# AMS_MCU.net
KiCad netlist of a schematic drawn in Altium Designer
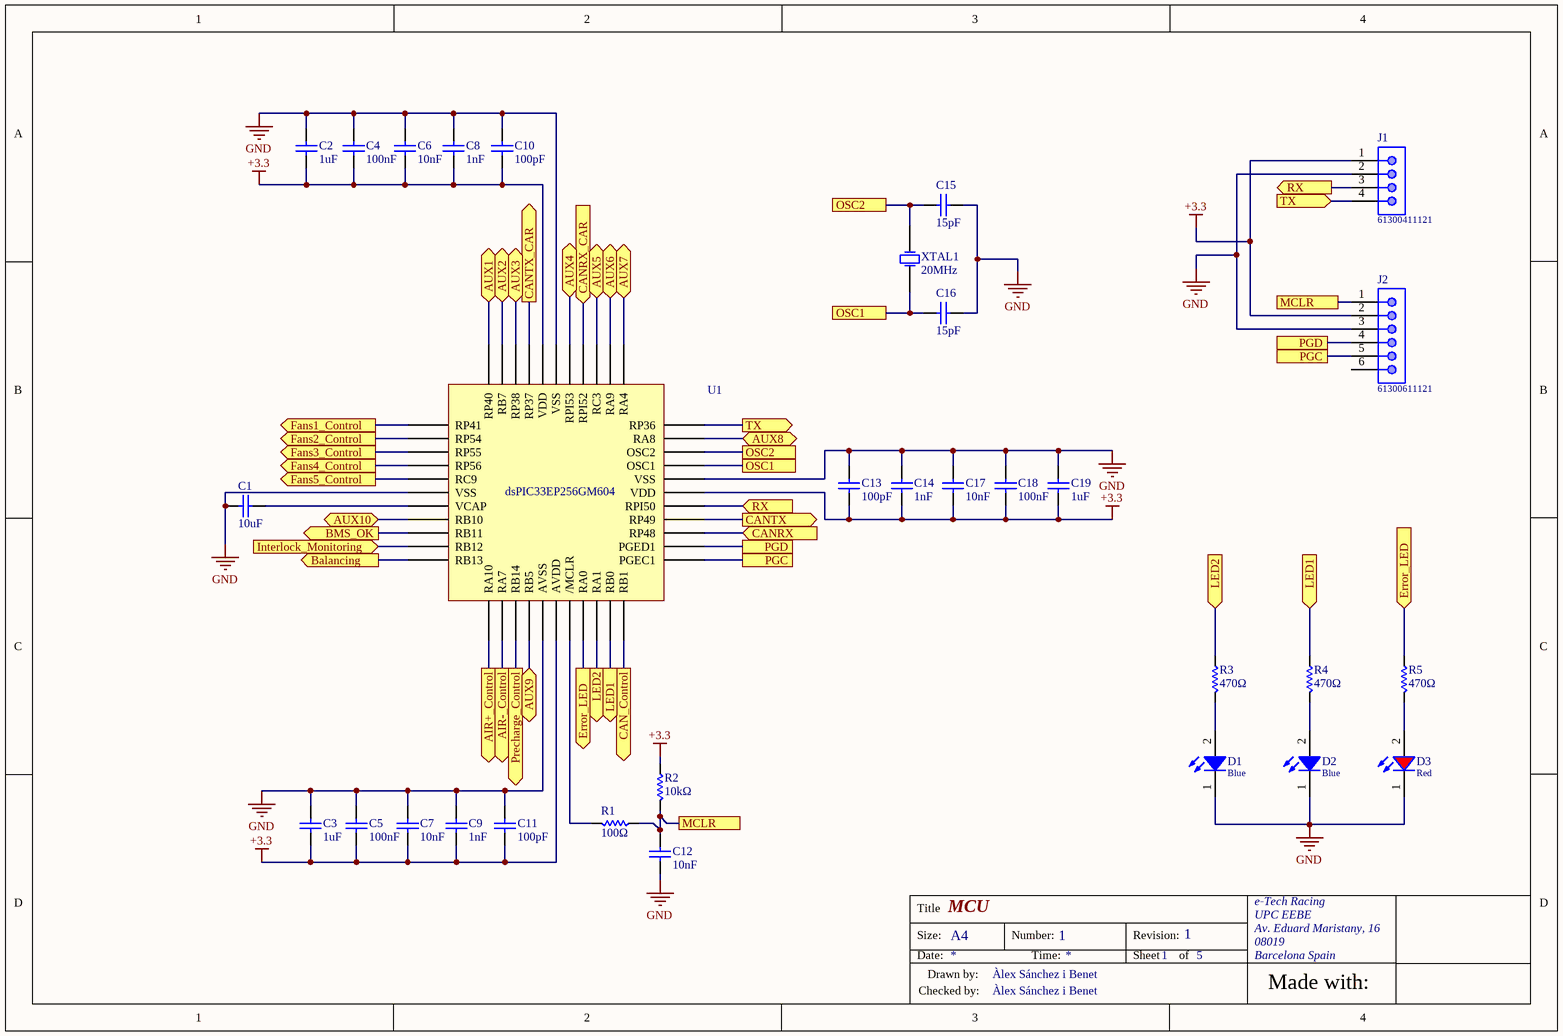
[diagram p0: AMS_MCU.SchDoc]

(export (version "E")
  (design (tool "Eeschema 10.0.6"))
  (components
    (comp (ref "C1")
      (value "10uF")
      (footprint "0805_2x1.25x1.25mm_Reflow Soldering")
      (description "WCAP-CSGP Ceramic Capacitors, 0805, X5R, 16V, 10uF")
      (fields (field (name "PART NUMBER") "885012107014") (field (name "PUBLISHER") "Wurth Elektronik"))
      (libsource (lib "Components_Library") (part "885012107014"))
    )
    (comp (ref "C2")
      (value "1uF")
      (footprint "0805_2x1.25x1.25mm_Reflow Soldering")
      (description "WCAP-CSGP Ceramic Capacitors, 0805, X7R, 50V, 1uF")
      (fields (field (name "PART NUMBER") "885012207103") (field (name "PUBLISHER") "Wurth Elektronik"))
      (libsource (lib "Components_Library") (part "885012207103"))
    )
    (comp (ref "C3")
      (value "1uF")
      (footprint "0805_2x1.25x1.25mm_Reflow Soldering")
      (description "WCAP-CSGP Ceramic Capacitors, 0805, X7R, 50V, 1uF")
      (fields (field (name "PART NUMBER") "885012207103") (field (name "PUBLISHER") "Wurth Elektronik"))
      (libsource (lib "Components_Library") (part "885012207103"))
    )
    (comp (ref "C4")
      (value "100nF")
      (footprint "0805_2x1.25x0.8mm_Reflow Soldering")
      (description "WCAP-CSGP Ceramic Capacitors, 0805, X7R, 50V, 100nF")
      (fields (field (name "PART NUMBER") "885012207098") (field (name "PUBLISHER") "Wurth Elektronik"))
      (libsource (lib "Components_Library") (part "885012207098"))
    )
    (comp (ref "C5")
      (value "100nF")
      (footprint "0805_2x1.25x0.8mm_Reflow Soldering")
      (description "WCAP-CSGP Ceramic Capacitors, 0805, X7R, 50V, 100nF")
      (fields (field (name "PART NUMBER") "885012207098") (field (name "PUBLISHER") "Wurth Elektronik"))
      (libsource (lib "Components_Library") (part "885012207098"))
    )
    (comp (ref "C6")
      (value "10nF")
      (footprint "0805_2x1.25x0.8mm_Reflow Soldering")
      (description "WCAP-CSGP Ceramic Capacitors, 0805, X7R, 50V, 10nF")
      (fields (field (name "PART NUMBER") "885012207092") (field (name "PUBLISHER") "Wurth Elektronik"))
      (libsource (lib "Components_Library") (part "885012207092"))
    )
    (comp (ref "C7")
      (value "10nF")
      (footprint "0805_2x1.25x0.8mm_Reflow Soldering")
      (description "WCAP-CSGP Ceramic Capacitors, 0805, X7R, 50V, 10nF")
      (fields (field (name "PART NUMBER") "885012207092") (field (name "PUBLISHER") "Wurth Elektronik"))
      (libsource (lib "Components_Library") (part "885012207092"))
    )
    (comp (ref "C8")
      (value "1nF")
      (footprint "0805_2x1.25x0.8mm_Reflow Soldering")
      (description "WCAP-CSGP Ceramic Capacitors, 0805, NP0, 50V, 1nF")
      (fields (field (name "PART NUMBER") "885012007063") (field (name "PUBLISHER") "Wurth Elektronik"))
      (libsource (lib "Components_Library") (part "885012007063"))
    )
    (comp (ref "C9")
      (value "1nF")
      (footprint "0805_2x1.25x0.8mm_Reflow Soldering")
      (description "WCAP-CSGP Ceramic Capacitors, 0805, NP0, 50V, 1nF")
      (fields (field (name "PART NUMBER") "885012007063") (field (name "PUBLISHER") "Wurth Elektronik"))
      (libsource (lib "Components_Library") (part "885012007063"))
    )
    (comp (ref "C10")
      (value "100pF")
      (footprint "0805_2x1.25x0.6mm_Reflow Soldering")
      (description "WCAP-CSGP Ceramic Capacitors, 0805, NP0, 50V, 100pF")
      (fields (field (name "PART NUMBER") "885012007057") (field (name "PUBLISHER") "Wurth Elektronik"))
      (libsource (lib "Components_Library") (part "885012007057"))
    )
    (comp (ref "C11")
      (value "100pF")
      (footprint "0805_2x1.25x0.6mm_Reflow Soldering")
      (description "WCAP-CSGP Ceramic Capacitors, 0805, NP0, 50V, 100pF")
      (fields (field (name "PART NUMBER") "885012007057") (field (name "PUBLISHER") "Wurth Elektronik"))
      (libsource (lib "Components_Library") (part "885012007057"))
    )
    (comp (ref "C12")
      (value "10nF")
      (footprint "0805_2x1.25x0.8mm_Reflow Soldering")
      (description "WCAP-CSGP Ceramic Capacitors, 0805, X7R, 50V, 10nF")
      (fields (field (name "PART NUMBER") "885012207092") (field (name "PUBLISHER") "Wurth Elektronik"))
      (libsource (lib "Components_Library") (part "885012207092"))
    )
    (comp (ref "C13")
      (value "100pF")
      (footprint "0805_2x1.25x0.6mm_Reflow Soldering")
      (description "WCAP-CSGP Ceramic Capacitors, 0805, NP0, 50V, 100pF")
      (fields (field (name "PART NUMBER") "885012007057") (field (name "PUBLISHER") "Wurth Elektronik"))
      (libsource (lib "Components_Library") (part "885012007057"))
    )
    (comp (ref "C14")
      (value "1nF")
      (footprint "0805_2x1.25x0.8mm_Reflow Soldering")
      (description "WCAP-CSGP Ceramic Capacitors, 0805, NP0, 50V, 1nF")
      (fields (field (name "PART NUMBER") "885012007063") (field (name "PUBLISHER") "Wurth Elektronik"))
      (libsource (lib "Components_Library") (part "885012007063"))
    )
    (comp (ref "C15")
      (value "15pF")
      (footprint "0805_2x1.25x0.6mm_Reflow Soldering")
      (description "WCAP-CSGP Ceramic Capacitors, 0805, NP0, 50V, 15pF")
      (fields (field (name "PART NUMBER") "885012007052") (field (name "PUBLISHER") "Wurth Elektronik"))
      (libsource (lib "Components_Library") (part "885012007052"))
    )
    (comp (ref "C16")
      (value "15pF")
      (footprint "0805_2x1.25x0.6mm_Reflow Soldering")
      (description "WCAP-CSGP Ceramic Capacitors, 0805, NP0, 50V, 15pF")
      (fields (field (name "PART NUMBER") "885012007052") (field (name "PUBLISHER") "Wurth Elektronik"))
      (libsource (lib "Components_Library") (part "885012007052"))
    )
    (comp (ref "C17")
      (value "10nF")
      (footprint "0805_2x1.25x0.8mm_Reflow Soldering")
      (description "WCAP-CSGP Ceramic Capacitors, 0805, X7R, 50V, 10nF")
      (fields (field (name "PART NUMBER") "885012207092") (field (name "PUBLISHER") "Wurth Elektronik"))
      (libsource (lib "Components_Library") (part "885012207092"))
    )
    (comp (ref "C18")
      (value "100nF")
      (footprint "0805_2x1.25x0.8mm_Reflow Soldering")
      (description "WCAP-CSGP Ceramic Capacitors, 0805, X7R, 50V, 100nF")
      (fields (field (name "PART NUMBER") "885012207098") (field (name "PUBLISHER") "Wurth Elektronik"))
      (libsource (lib "Components_Library") (part "885012207098"))
    )
    (comp (ref "C19")
      (value "1uF")
      (footprint "0805_2x1.25x1.25mm_Reflow Soldering")
      (description "WCAP-CSGP Ceramic Capacitors, 0805, X7R, 50V, 1uF")
      (fields (field (name "PART NUMBER") "885012207103") (field (name "PUBLISHER") "Wurth Elektronik"))
      (libsource (lib "Components_Library") (part "885012207103"))
    )
    (comp (ref "D1")
      (value "Blue")
      (footprint "WL-SMCW_0805")
      (description "SMT Mono-color Chip LED Waterclear WL-SMCW, size 0805, Blue, 3.2 V, 140 deg, 145 mcd")
      (fields (field (name "PART NUMBER") "150080BS75000") (field (name "PUBLISHER") "Wurth Elektronik"))
      (libsource (lib "Components_Library") (part "150080BS75000"))
    )
    (comp (ref "D2")
      (value "Blue")
      (footprint "WL-SMCW_0805")
      (description "SMT Mono-color Chip LED Waterclear WL-SMCW, size 0805, Blue, 3.2 V, 140 deg, 145 mcd")
      (fields (field (name "PART NUMBER") "150080BS75000") (field (name "PUBLISHER") "Wurth Elektronik"))
      (libsource (lib "Components_Library") (part "150080BS75000"))
    )
    (comp (ref "D3")
      (value "Red")
      (footprint "WL-SMCW_0805")
      (description "SMT Mono-color Chip LED Waterclear WL-SMCW, size 0805, Red, 2 V, 140 deg, 150 mcd")
      (fields (field (name "PART NUMBER") "150080RS75000") (field (name "PUBLISHER") "Wurth Elektronik"))
      (libsource (lib "Components_Library") (part "150080RS75000"))
    )
    (comp (ref "J1")
      (value "61300411121")
      (footprint "61300411121")
      (description "THT Vertical Pin Header WR-PHD, Pitch 2.54 mm, Single Row, 4 pins")
      (fields (field (name "PUBLISHER") "Wurth Elektronik"))
      (libsource (lib "Components_Library") (part "61300411121"))
    )
    (comp (ref "J2")
      (value "61300611121")
      (footprint "61300611121")
      (description "THT Vertical Pin Header WR-PHD, Pitch 2.54 mm, Single Row, 6 pins")
      (fields (field (name "PUBLISHER") "Wurth Elektronik"))
      (libsource (lib "Components_Library") (part "61300611121"))
    )
    (comp (ref "R1")
      (value "100Ω")
      (footprint "CR0805")
      (description "Chip Resistor 0805")
      (fields (field (name "MANUFACTURER") "Bourns"))
      (libsource (lib "Components_Library") (part "CR0805-FX-1000ELF"))
    )
    (comp (ref "R2")
      (value "10kΩ")
      (footprint "CR0805")
      (description "Chip Resistor 0805")
      (fields (field (name "MANUFACTURER") "Bourns"))
      (libsource (lib "Components_Library") (part "CR0805-JW-103ELF"))
    )
    (comp (ref "R3")
      (value "470Ω")
      (footprint "CR0805")
      (description "Chip Resistor 0805")
      (fields (field (name "MANUFACTURER") "Bourns"))
      (libsource (lib "Components_Library") (part "CR0805-FX-4700GLF"))
    )
    (comp (ref "R4")
      (value "470Ω")
      (footprint "CR0805")
      (description "Chip Resistor 0805")
      (fields (field (name "MANUFACTURER") "Bourns"))
      (libsource (lib "Components_Library") (part "CR0805-FX-4700GLF"))
    )
    (comp (ref "R5")
      (value "470Ω")
      (footprint "CR0805")
      (description "Chip Resistor 0805")
      (fields (field (name "MANUFACTURER") "Bourns"))
      (libsource (lib "Components_Library") (part "CR0805-FX-4700GLF"))
    )
    (comp (ref "U1")
      (value "dsPIC33EP256GM604")
      (footprint "dsPIC33EP256GM604")
      (description "16-Bit Digital Signal Controller with High-Speed PWM, Op Amps and Advanced Analog Features")
      (fields (field (name "MANUFACTURER") "Microchip"))
      (libsource (lib "Components_Library") (part "dsPIC33EP256GM604"))
    )
    (comp (ref "XTAL1")
      (value "20MHz")
      (footprint "830028710")
      (description "Industry standard SMD crystal WE-XTAL Quartz Crystal")
      (fields (field (name "MANUFACTURER") "Wurth Elektronik"))
      (libsource (lib "Components_Library") (part "830028710"))
    )
  )
  (nets
    (net (code "1") (name "+3.3") (class "Default")
      (node (ref "C10") (pin "1") (pinfunction "1_1") (pintype "passive"))
      (node (ref "C11") (pin "1") (pinfunction "1_1") (pintype "passive"))
      (node (ref "C13") (pin "1") (pinfunction "1_1") (pintype "passive"))
      (node (ref "C14") (pin "1") (pinfunction "1_1") (pintype "passive"))
      (node (ref "C17") (pin "1") (pinfunction "1_1") (pintype "passive"))
      (node (ref "C18") (pin "1") (pinfunction "1_1") (pintype "passive"))
      (node (ref "C19") (pin "1") (pinfunction "1_1") (pintype "passive"))
      (node (ref "C2") (pin "1") (pinfunction "1_1") (pintype "passive"))
      (node (ref "C3") (pin "1") (pinfunction "1_1") (pintype "passive"))
      (node (ref "C4") (pin "1") (pinfunction "1_1") (pintype "passive"))
      (node (ref "C5") (pin "1") (pinfunction "1_1") (pintype "passive"))
      (node (ref "C6") (pin "1") (pinfunction "1_1") (pintype "passive"))
      (node (ref "C7") (pin "1") (pinfunction "1_1") (pintype "passive"))
      (node (ref "C8") (pin "1") (pinfunction "1_1") (pintype "passive"))
      (node (ref "C9") (pin "1") (pinfunction "1_1") (pintype "passive"))
      (node (ref "J1") (pin "1") (pinfunction "1_1") (pintype "passive"))
      (node (ref "J2") (pin "2") (pinfunction "2_2") (pintype "passive"))
      (node (ref "R2") (pin "2") (pinfunction "2_2") (pintype "passive"))
      (node (ref "U1") (pin "17") (pinfunction "AVDD_17") (pintype "passive"))
      (node (ref "U1") (pin "28") (pinfunction "VDD_28") (pintype "passive"))
      (node (ref "U1") (pin "40") (pinfunction "VDD_40") (pintype "passive"))
    )
    (net (code "2") (name "/AIR+_Control") (class "Default")
      (node (ref "U1") (pin "12") (pinfunction "RA10_12") (pintype "passive"))
    )
    (net (code "3") (name "/AIR-_Control") (class "Default")
      (node (ref "U1") (pin "13") (pinfunction "RA7_13") (pintype "passive"))
    )
    (net (code "4") (name "/AUX1") (class "Default")
      (node (ref "U1") (pin "44") (pinfunction "RP40_44") (pintype "passive"))
    )
    (net (code "5") (name "/AUX2") (class "Default")
      (node (ref "U1") (pin "43") (pinfunction "RB7_43") (pintype "passive"))
    )
    (net (code "6") (name "/AUX3") (class "Default")
      (node (ref "U1") (pin "42") (pinfunction "RP38_42") (pintype "passive"))
    )
    (net (code "7") (name "/AUX4") (class "Default")
      (node (ref "U1") (pin "38") (pinfunction "RPI53_38") (pintype "passive"))
    )
    (net (code "8") (name "/AUX5") (class "Default")
      (node (ref "U1") (pin "36") (pinfunction "RC3_36") (pintype "passive"))
    )
    (net (code "9") (name "/AUX6") (class "Default")
      (node (ref "U1") (pin "35") (pinfunction "RA9_35") (pintype "passive"))
    )
    (net (code "10") (name "/AUX7") (class "Default")
      (node (ref "U1") (pin "34") (pinfunction "RA4_34") (pintype "passive"))
    )
    (net (code "11") (name "/AUX8") (class "Default")
      (node (ref "U1") (pin "32") (pinfunction "RA8_32") (pintype "passive"))
    )
    (net (code "12") (name "/AUX9") (class "Default")
      (node (ref "U1") (pin "15") (pinfunction "RB5_15") (pintype "passive"))
    )
    (net (code "13") (name "/AUX10") (class "Default")
      (node (ref "U1") (pin "8") (pinfunction "RB10_8") (pintype "passive"))
    )
    (net (code "14") (name "/BMS_OK") (class "Default")
      (node (ref "U1") (pin "9") (pinfunction "RB11_9") (pintype "passive"))
    )
    (net (code "15") (name "/Balancing") (class "Default")
      (node (ref "U1") (pin "11") (pinfunction "RB13_11") (pintype "passive"))
    )
    (net (code "16") (name "/CANRX") (class "Default")
      (node (ref "U1") (pin "25") (pinfunction "RP48_25") (pintype "passive"))
    )
    (net (code "17") (name "/CANRX_CAR") (class "Default")
      (node (ref "U1") (pin "37") (pinfunction "RPI52_37") (pintype "passive"))
    )
    (net (code "18") (name "/CANTX") (class "Default")
      (node (ref "U1") (pin "26") (pinfunction "RP49_26") (pintype "passive"))
    )
    (net (code "19") (name "/CANTX_CAR") (class "Default")
      (node (ref "U1") (pin "41") (pinfunction "RP37_41") (pintype "passive"))
    )
    (net (code "20") (name "/CAN_Control") (class "Default")
      (node (ref "U1") (pin "22") (pinfunction "RB1_22") (pintype "passive"))
    )
    (net (code "21") (name "/Error_LED") (class "Default")
      (node (ref "R5") (pin "2") (pinfunction "2_2") (pintype "passive"))
      (node (ref "U1") (pin "19") (pinfunction "RA0_19") (pintype "passive"))
    )
    (net (code "22") (name "/Fans1_Control") (class "Default")
      (node (ref "U1") (pin "1") (pinfunction "RP41_1") (pintype "passive"))
    )
    (net (code "23") (name "/Fans2_Control") (class "Default")
      (node (ref "U1") (pin "2") (pinfunction "RP54_2") (pintype "passive"))
    )
    (net (code "24") (name "/Fans3_Control") (class "Default")
      (node (ref "U1") (pin "3") (pinfunction "RP55_3") (pintype "passive"))
    )
    (net (code "25") (name "/Fans4_Control") (class "Default")
      (node (ref "U1") (pin "4") (pinfunction "RP56_4") (pintype "passive"))
    )
    (net (code "26") (name "/Fans5_Control") (class "Default")
      (node (ref "U1") (pin "5") (pinfunction "RC9_5") (pintype "passive"))
    )
    (net (code "27") (name "/Interlock_Monitoring") (class "Default")
      (node (ref "U1") (pin "10") (pinfunction "RB12_10") (pintype "passive"))
    )
    (net (code "28") (name "/LED1") (class "Default")
      (node (ref "R4") (pin "2") (pinfunction "2_2") (pintype "passive"))
      (node (ref "U1") (pin "21") (pinfunction "RB0_21") (pintype "passive"))
    )
    (net (code "29") (name "/LED2") (class "Default")
      (node (ref "R3") (pin "2") (pinfunction "2_2") (pintype "passive"))
      (node (ref "U1") (pin "20") (pinfunction "RA1_20") (pintype "passive"))
    )
    (net (code "30") (name "/MCLR") (class "Default")
      (node (ref "C12") (pin "2") (pinfunction "2_2") (pintype "passive"))
      (node (ref "J2") (pin "1") (pinfunction "1_1") (pintype "passive"))
      (node (ref "R1") (pin "2") (pinfunction "2_2") (pintype "passive"))
      (node (ref "R2") (pin "1") (pinfunction "1_1") (pintype "passive"))
    )
    (net (code "31") (name "/OSC1") (class "Default")
      (node (ref "C16") (pin "1") (pinfunction "1_1") (pintype "passive"))
      (node (ref "U1") (pin "30") (pinfunction "OSC1_30") (pintype "passive"))
      (node (ref "XTAL1") (pin "1") (pinfunction "OSC1_1") (pintype "passive"))
    )
    (net (code "32") (name "/OSC2") (class "Default")
      (node (ref "C15") (pin "1") (pinfunction "1_1") (pintype "passive"))
      (node (ref "U1") (pin "31") (pinfunction "OSC2_31") (pintype "passive"))
      (node (ref "XTAL1") (pin "2") (pinfunction "OSC2_2") (pintype "passive"))
    )
    (net (code "33") (name "/PGC") (class "Default")
      (node (ref "J2") (pin "5") (pinfunction "5_5") (pintype "passive"))
      (node (ref "U1") (pin "23") (pinfunction "PGEC1_23") (pintype "passive"))
    )
    (net (code "34") (name "/PGD") (class "Default")
      (node (ref "J2") (pin "4") (pinfunction "4_4") (pintype "passive"))
      (node (ref "U1") (pin "24") (pinfunction "PGED1_24") (pintype "passive"))
    )
    (net (code "35") (name "/Precharge_Control") (class "Default")
      (node (ref "U1") (pin "14") (pinfunction "RB14_14") (pintype "passive"))
    )
    (net (code "36") (name "/RX") (class "Default")
      (node (ref "J1") (pin "3") (pinfunction "3_3") (pintype "passive"))
      (node (ref "U1") (pin "27") (pinfunction "RPI50_27") (pintype "passive"))
    )
    (net (code "37") (name "/TX") (class "Default")
      (node (ref "J1") (pin "4") (pinfunction "4_4") (pintype "passive"))
      (node (ref "U1") (pin "33") (pinfunction "RP36_33") (pintype "passive"))
    )
    (net (code "38") (name "GND") (class "Default")
      (node (ref "C1") (pin "2") (pinfunction "2_2") (pintype "passive"))
      (node (ref "C10") (pin "2") (pinfunction "2_2") (pintype "passive"))
      (node (ref "C11") (pin "2") (pinfunction "2_2") (pintype "passive"))
      (node (ref "C12") (pin "1") (pinfunction "1_1") (pintype "passive"))
      (node (ref "C13") (pin "2") (pinfunction "2_2") (pintype "passive"))
      (node (ref "C14") (pin "2") (pinfunction "2_2") (pintype "passive"))
      (node (ref "C15") (pin "2") (pinfunction "2_2") (pintype "passive"))
      (node (ref "C16") (pin "2") (pinfunction "2_2") (pintype "passive"))
      (node (ref "C17") (pin "2") (pinfunction "2_2") (pintype "passive"))
      (node (ref "C18") (pin "2") (pinfunction "2_2") (pintype "passive"))
      (node (ref "C19") (pin "2") (pinfunction "2_2") (pintype "passive"))
      (node (ref "C2") (pin "2") (pinfunction "2_2") (pintype "passive"))
      (node (ref "C3") (pin "2") (pinfunction "2_2") (pintype "passive"))
      (node (ref "C4") (pin "2") (pinfunction "2_2") (pintype "passive"))
      (node (ref "C5") (pin "2") (pinfunction "2_2") (pintype "passive"))
      (node (ref "C6") (pin "2") (pinfunction "2_2") (pintype "passive"))
      (node (ref "C7") (pin "2") (pinfunction "2_2") (pintype "passive"))
      (node (ref "C8") (pin "2") (pinfunction "2_2") (pintype "passive"))
      (node (ref "C9") (pin "2") (pinfunction "2_2") (pintype "passive"))
      (node (ref "D1") (pin "1") (pinfunction "K_1") (pintype "passive"))
      (node (ref "D2") (pin "1") (pinfunction "K_1") (pintype "passive"))
      (node (ref "D3") (pin "1") (pinfunction "K_1") (pintype "passive"))
      (node (ref "J1") (pin "2") (pinfunction "2_2") (pintype "passive"))
      (node (ref "J2") (pin "3") (pinfunction "3_3") (pintype "passive"))
      (node (ref "U1") (pin "16") (pinfunction "AVSS_16") (pintype "passive"))
      (node (ref "U1") (pin "29") (pinfunction "VSS_29") (pintype "passive"))
      (node (ref "U1") (pin "39") (pinfunction "VSS_39") (pintype "passive"))
      (node (ref "U1") (pin "6") (pinfunction "VSS_6") (pintype "passive"))
    )
    (net (code "39") (name "Net-(D1-A)") (class "Default")
      (node (ref "D1") (pin "2") (pinfunction "A_2") (pintype "passive"))
      (node (ref "R3") (pin "1") (pinfunction "1_1") (pintype "passive"))
    )
    (net (code "40") (name "Net-(D2-A)") (class "Default")
      (node (ref "D2") (pin "2") (pinfunction "A_2") (pintype "passive"))
      (node (ref "R4") (pin "1") (pinfunction "1_1") (pintype "passive"))
    )
    (net (code "41") (name "Net-(D3-A)") (class "Default")
      (node (ref "D3") (pin "2") (pinfunction "A_2") (pintype "passive"))
      (node (ref "R5") (pin "1") (pinfunction "1_1") (pintype "passive"))
    )
    (net (code "42") (name "Net-(U1-VCAP)") (class "Default")
      (node (ref "C1") (pin "1") (pinfunction "1_1") (pintype "passive"))
      (node (ref "U1") (pin "7") (pinfunction "VCAP_7") (pintype "passive"))
    )
    (net (code "43") (name "Net-(U1-{slash}MCLR)") (class "Default")
      (node (ref "R1") (pin "1") (pinfunction "1_1") (pintype "passive"))
      (node (ref "U1") (pin "18") (pinfunction "/MCLR_18") (pintype "passive"))
    )
    (net (code "44") (name "unconnected-(J2-Pad6)") (class "Default")
      (node (ref "J2") (pin "6") (pinfunction "6_6") (pintype "passive"))
    )
  )
)
